# Grove_-_Haptic_Motor_v0_9.net
KiCad netlist of a schematic drawn in EAGLE
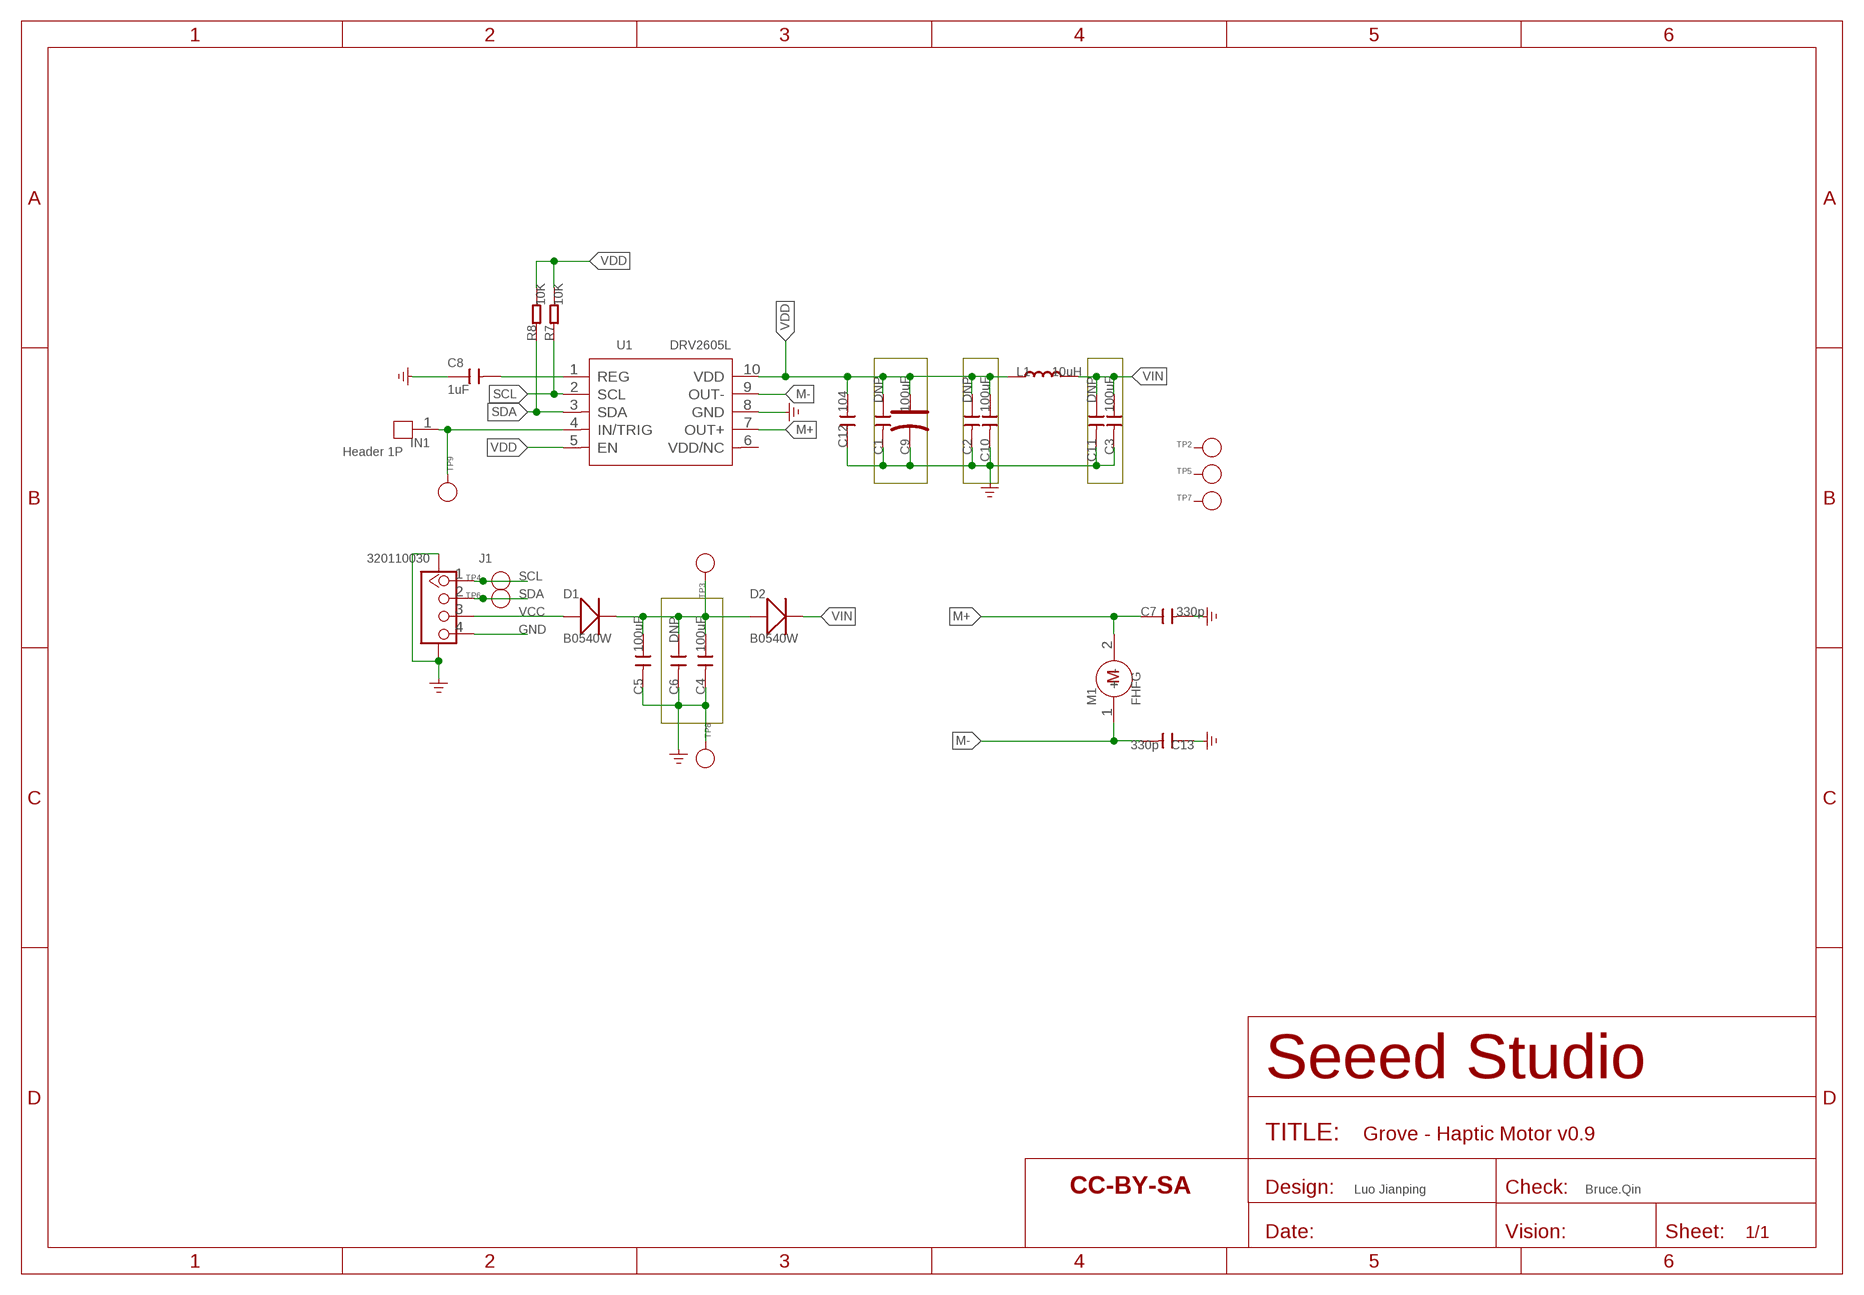
[diagram p0: schematic, sheet 1]

(export (version "E")
  (design (tool "Eeschema 10.0.6"))
  (components
    (comp (ref "C1")
      (value "DNP")
      (footprint "eagle-import:C0805")
      (libsource (lib "eagle-import") (part "CAP-0805"))
    )
    (comp (ref "C2")
      (value "DNP")
      (footprint "eagle-import:C0805")
      (libsource (lib "eagle-import") (part "CAP-0805"))
    )
    (comp (ref "C3")
      (value "100uF")
      (footprint "eagle-import:C1206")
      (libsource (lib "eagle-import") (part "CAP-1206"))
    )
    (comp (ref "C4")
      (value "100uF")
      (footprint "eagle-import:C1206")
      (libsource (lib "eagle-import") (part "CAP-1206"))
    )
    (comp (ref "C5")
      (value "100uF")
      (footprint "eagle-import:C0603")
      (libsource (lib "eagle-import") (part "CAP-0603"))
    )
    (comp (ref "C6")
      (value "DNP")
      (footprint "eagle-import:C0805")
      (libsource (lib "eagle-import") (part "CAP-0805"))
    )
    (comp (ref "C7")
      (value "330p")
      (footprint "eagle-import:C0603")
      (libsource (lib "eagle-import") (part "CAP-0603"))
    )
    (comp (ref "C8")
      (value "1uF")
      (footprint "eagle-import:C0603")
      (libsource (lib "eagle-import") (part "CAP-0603"))
    )
    (comp (ref "C9")
      (value "100uF")
      (footprint "eagle-import:AVX-B")
      (libsource (lib "eagle-import") (part "CAP-POLAR-AVX-B"))
    )
    (comp (ref "C10")
      (value "100uF")
      (footprint "eagle-import:C1206")
      (libsource (lib "eagle-import") (part "CAP-1206"))
    )
    (comp (ref "C11")
      (value "DNP")
      (footprint "eagle-import:C0805")
      (libsource (lib "eagle-import") (part "CAP-0805"))
    )
    (comp (ref "C12")
      (value "104")
      (footprint "eagle-import:C0603")
      (libsource (lib "eagle-import") (part "CAP-0603"))
    )
    (comp (ref "C13")
      (value "330p")
      (footprint "eagle-import:C0603")
      (libsource (lib "eagle-import") (part "CAP-0603"))
    )
    (comp (ref "D1")
      (value "B0540W")
      (footprint "eagle-import:SOD-123")
      (libsource (lib "eagle-import") (part "DIODE'1206'"))
    )
    (comp (ref "D2")
      (value "B0540W")
      (footprint "eagle-import:SOD-123")
      (libsource (lib "eagle-import") (part "DIODE'1206'"))
    )
    (comp (ref "IN1")
      (value "Header 1P")
      (footprint "eagle-import:1P-65_35MIL")
      (libsource (lib "eagle-import") (part "HEADER-1P-35"))
    )
    (comp (ref "J1")
      (value "320110030")
      (footprint "eagle-import:HW4-SMD-2.0")
      (libsource (lib "eagle-import") (part "GROVE-CONNECTOR-SMD'DD'"))
    )
    (comp (ref "L1")
      (value "10uH")
      (footprint "eagle-import:L0806")
      (libsource (lib "eagle-import") (part "INDUCTOR/FERRITE-BEAD'0806'"))
    )
    (comp (ref "M1")
      (value "FHFG")
      (footprint "eagle-import:MTR2-SMD-D11.2MM")
      (libsource (lib "eagle-import") (part "MOTOR-EXT_MOUDLE_1CM"))
    )
    (comp (ref "R7")
      (value "10K")
      (footprint "eagle-import:R0603")
      (libsource (lib "eagle-import") (part "RES-0603"))
    )
    (comp (ref "R8")
      (value "10K")
      (footprint "eagle-import:R0603")
      (libsource (lib "eagle-import") (part "RES-0603"))
    )
    (comp (ref "TP2")
      (value "PAD-TEST-POINT'4545'")
      (footprint "eagle-import:TP_4545")
      (fields (field (name "PARTNO") "DNP"))
      (libsource (lib "eagle-import") (part "PAD-TEST-POINT'4545'"))
    )
    (comp (ref "TP3")
      (value "PAD-TEST-POINT'4545'")
      (footprint "eagle-import:TP_4545")
      (fields (field (name "PARTNO") "DNP"))
      (libsource (lib "eagle-import") (part "PAD-TEST-POINT'4545'"))
    )
    (comp (ref "TP4")
      (value "PAD-TEST-POINT'4545'")
      (footprint "eagle-import:TP_4545")
      (fields (field (name "PARTNO") "DNP"))
      (libsource (lib "eagle-import") (part "PAD-TEST-POINT'4545'"))
    )
    (comp (ref "TP5")
      (value "PAD-TEST-POINT'4545'")
      (footprint "eagle-import:TP_4545")
      (fields (field (name "PARTNO") "DNP"))
      (libsource (lib "eagle-import") (part "PAD-TEST-POINT'4545'"))
    )
    (comp (ref "TP6")
      (value "PAD-TEST-POINT'4545'")
      (footprint "eagle-import:TP_4545")
      (fields (field (name "PARTNO") "DNP"))
      (libsource (lib "eagle-import") (part "PAD-TEST-POINT'4545'"))
    )
    (comp (ref "TP7")
      (value "PAD-TEST-POINT'4545'")
      (footprint "eagle-import:TP_4545")
      (fields (field (name "PARTNO") "DNP"))
      (libsource (lib "eagle-import") (part "PAD-TEST-POINT'4545'"))
    )
    (comp (ref "TP8")
      (value "PAD-TEST-POINT'4545'")
      (footprint "eagle-import:TP_4545")
      (fields (field (name "PARTNO") "DNP"))
      (libsource (lib "eagle-import") (part "PAD-TEST-POINT'4545'"))
    )
    (comp (ref "TP9")
      (value "PAD-TEST-POINT'4545'")
      (footprint "eagle-import:TP_4545")
      (fields (field (name "PARTNO") "DNP"))
      (libsource (lib "eagle-import") (part "PAD-TEST-POINT'4545'"))
    )
    (comp (ref "U$9")
      (value "SEEEDSTUDIO-OPEN-SCH-FRAME")
      (footprint "eagle-import:SEEEDSTUDIO-PCB-FRAME")
      (libsource (lib "eagle-import") (part "SEEEDSTUDIO-OPEN-SCH-FRAME"))
    )
    (comp (ref "U1")
      (value "DRV2605L")
      (footprint "eagle-import:VSSOP10-0.5-3X3MM")
      (libsource (lib "eagle-import") (part "SENSOR-DRV2605L"))
    )
  )
  (nets
    (net (code "1") (name "/VCC") (class "Default")
      (node (ref "D1") (pin "+") (pinfunction "+_+") (pintype "passive"))
      (node (ref "J1") (pin "3") (pinfunction "3_3") (pintype "bidirectional"))
    )
    (net (code "2") (name "GND_POWER") (class "Default")
      (node (ref "C1") (pin "2") (pinfunction "2_2") (pintype "passive"))
      (node (ref "C10") (pin "2") (pinfunction "2_2") (pintype "passive"))
      (node (ref "C11") (pin "2") (pinfunction "2_2") (pintype "passive"))
      (node (ref "C12") (pin "1") (pinfunction "1_1") (pintype "passive"))
      (node (ref "C13") (pin "1") (pinfunction "1_1") (pintype "passive"))
      (node (ref "C2") (pin "2") (pinfunction "2_2") (pintype "passive"))
      (node (ref "C3") (pin "2") (pinfunction "2_2") (pintype "passive"))
      (node (ref "C4") (pin "2") (pinfunction "2_2") (pintype "passive"))
      (node (ref "C5") (pin "2") (pinfunction "2_2") (pintype "passive"))
      (node (ref "C6") (pin "2") (pinfunction "2_2") (pintype "passive"))
      (node (ref "C7") (pin "2") (pinfunction "2_2") (pintype "passive"))
      (node (ref "C8") (pin "1") (pinfunction "1_1") (pintype "passive"))
      (node (ref "C9") (pin "-") (pinfunction "-_-") (pintype "passive"))
      (node (ref "J1") (pin "4") (pinfunction "4_4") (pintype "bidirectional"))
      (node (ref "J1") (pin "SS1") (pinfunction "SS1_SS1") (pintype "bidirectional"))
      (node (ref "J1") (pin "SS2") (pinfunction "SS2_SS2") (pintype "bidirectional"))
      (node (ref "TP8") (pin "T") (pinfunction "T_T") (pintype "bidirectional"))
      (node (ref "U1") (pin "8") (pinfunction "GND_8") (pintype "bidirectional"))
    )
    (net (code "3") (name "M+") (class "Default")
      (node (ref "C7") (pin "1") (pinfunction "1_1") (pintype "passive"))
      (node (ref "M1") (pin "2") (pinfunction "-_2") (pintype "bidirectional"))
      (node (ref "U1") (pin "7") (pinfunction "OUT+_7") (pintype "bidirectional"))
    )
    (net (code "4") (name "M-") (class "Default")
      (node (ref "C13") (pin "2") (pinfunction "2_2") (pintype "passive"))
      (node (ref "M1") (pin "1") (pinfunction "+_1") (pintype "bidirectional"))
      (node (ref "U1") (pin "9") (pinfunction "OUT-_9") (pintype "bidirectional"))
    )
    (net (code "5") (name "Net-(C4-Pad1)") (class "Default")
      (node (ref "C4") (pin "1") (pinfunction "1_1") (pintype "passive"))
      (node (ref "C5") (pin "1") (pinfunction "1_1") (pintype "passive"))
      (node (ref "C6") (pin "1") (pinfunction "1_1") (pintype "passive"))
      (node (ref "D1") (pin "-") (pinfunction "-_-") (pintype "passive"))
      (node (ref "D2") (pin "+") (pinfunction "+_+") (pintype "passive"))
      (node (ref "TP3") (pin "T") (pinfunction "T_T") (pintype "bidirectional"))
    )
    (net (code "6") (name "Net-(U1-IN{slash}TRIG)") (class "Default")
      (node (ref "IN1") (pin "1") (pinfunction "1_1") (pintype "bidirectional"))
      (node (ref "TP9") (pin "T") (pinfunction "T_T") (pintype "bidirectional"))
      (node (ref "U1") (pin "4") (pinfunction "IN/TRIG_4") (pintype "bidirectional"))
    )
    (net (code "7") (name "Net-(U1-REG)") (class "Default")
      (node (ref "C8") (pin "2") (pinfunction "2_2") (pintype "passive"))
      (node (ref "U1") (pin "1") (pinfunction "REG_1") (pintype "bidirectional"))
    )
    (net (code "8") (name "SCL") (class "Default")
      (node (ref "J1") (pin "1") (pinfunction "1_1") (pintype "bidirectional"))
      (node (ref "R7") (pin "1") (pinfunction "1_1") (pintype "passive"))
      (node (ref "TP4") (pin "T") (pinfunction "T_T") (pintype "bidirectional"))
      (node (ref "U1") (pin "2") (pinfunction "SCL_2") (pintype "bidirectional"))
    )
    (net (code "9") (name "SDA") (class "Default")
      (node (ref "J1") (pin "2") (pinfunction "2_2") (pintype "bidirectional"))
      (node (ref "R8") (pin "1") (pinfunction "1_1") (pintype "passive"))
      (node (ref "TP6") (pin "T") (pinfunction "T_T") (pintype "bidirectional"))
      (node (ref "U1") (pin "3") (pinfunction "SDA_3") (pintype "bidirectional"))
    )
    (net (code "10") (name "VDD") (class "Default")
      (node (ref "C1") (pin "1") (pinfunction "1_1") (pintype "passive"))
      (node (ref "C10") (pin "1") (pinfunction "1_1") (pintype "passive"))
      (node (ref "C12") (pin "2") (pinfunction "2_2") (pintype "passive"))
      (node (ref "C2") (pin "1") (pinfunction "1_1") (pintype "passive"))
      (node (ref "C9") (pin "+") (pinfunction "+_+") (pintype "passive"))
      (node (ref "L1") (pin "1") (pinfunction "1_1") (pintype "passive"))
      (node (ref "R7") (pin "2") (pinfunction "2_2") (pintype "passive"))
      (node (ref "R8") (pin "2") (pinfunction "2_2") (pintype "passive"))
      (node (ref "U1") (pin "10") (pinfunction "VDD_10") (pintype "bidirectional"))
      (node (ref "U1") (pin "5") (pinfunction "EN_5") (pintype "bidirectional"))
    )
    (net (code "11") (name "VIN") (class "Default")
      (node (ref "C11") (pin "1") (pinfunction "1_1") (pintype "passive"))
      (node (ref "C3") (pin "1") (pinfunction "1_1") (pintype "passive"))
      (node (ref "D2") (pin "-") (pinfunction "-_-") (pintype "passive"))
      (node (ref "L1") (pin "2") (pinfunction "2_2") (pintype "passive"))
    )
    (net (code "12") (name "unconnected-(TP2-PadT)") (class "Default")
      (node (ref "TP2") (pin "T") (pinfunction "T_T") (pintype "bidirectional"))
    )
    (net (code "13") (name "unconnected-(TP5-PadT)") (class "Default")
      (node (ref "TP5") (pin "T") (pinfunction "T_T") (pintype "bidirectional"))
    )
    (net (code "14") (name "unconnected-(TP7-PadT)") (class "Default")
      (node (ref "TP7") (pin "T") (pinfunction "T_T") (pintype "bidirectional"))
    )
    (net (code "15") (name "unconnected-(U1-VDD{slash}NC-Pad6)") (class "Default")
      (node (ref "U1") (pin "6") (pinfunction "VDD/NC_6") (pintype "bidirectional"))
    )
  )
)
